# Encoder_AFE_incremental.net
KiCad netlist of a schematic drawn in Altium Designer
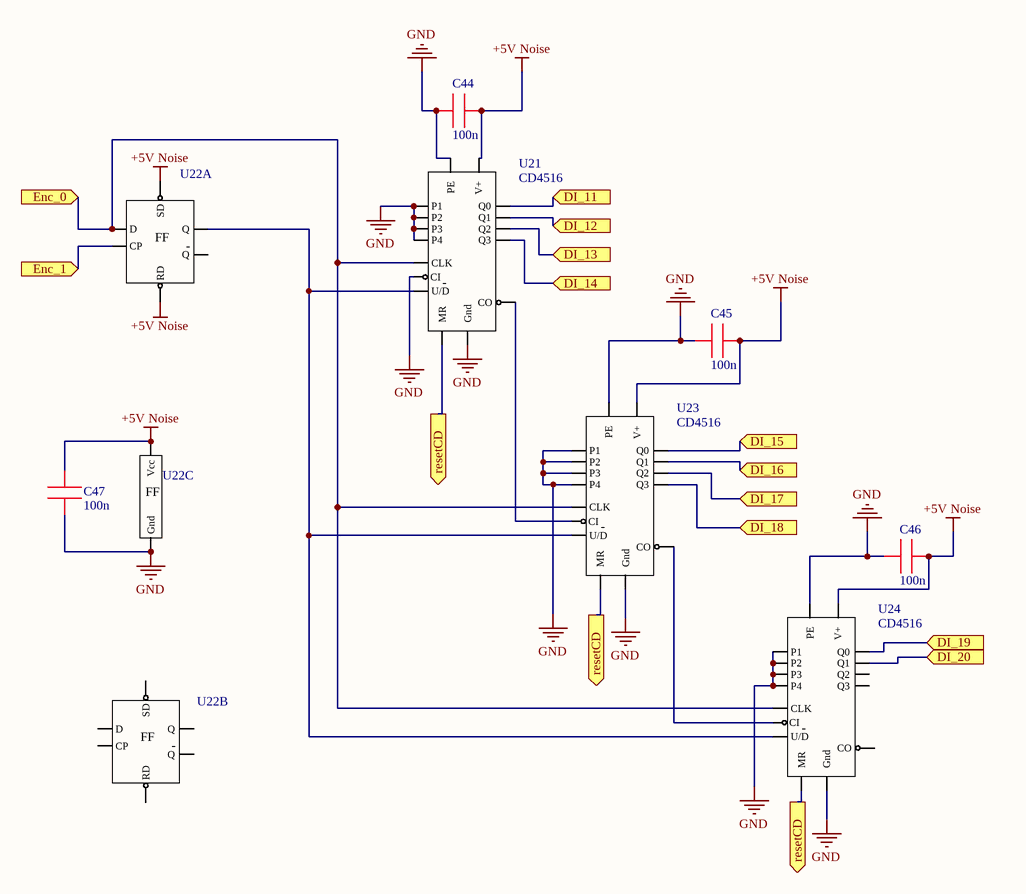
[diagram p0: Encoder AFE incremental.SchDoc]

(export (version "E")
  (design (tool "Eeschema 10.0.6"))
  (components
    (comp (ref "C44")
      (value "100n")
      (footprint "0603")
      (description "CC0603KRX7R9BB104")
      (libsource (lib "kontr") (part "0603 CAP"))
    )
    (comp (ref "C45")
      (value "100n")
      (footprint "0603")
      (description "CC0603KRX7R9BB104")
      (libsource (lib "kontr") (part "0603 CAP"))
    )
    (comp (ref "C46")
      (value "100n")
      (footprint "0603")
      (description "CC0603KRX7R9BB104")
      (libsource (lib "kontr") (part "0603 CAP"))
    )
    (comp (ref "C47")
      (value "100n")
      (footprint "0603")
      (description "CC0603KRX7R9BB104")
      (libsource (lib "kontr") (part "0603 CAP"))
    )
    (comp (ref "U21") (value "CD4516") (footprint "TSSOP-16") (libsource (lib "kontr") (part "CD4516")))
    (comp (ref "U22")
      (value "74HC74D")
      (footprint "SOIC 14 lead")
      (description "74HC74D,653")
      (libsource (lib "kontr") (part "74HC74D"))
    )
    (comp (ref "U23") (value "CD4516") (footprint "TSSOP-16") (libsource (lib "kontr") (part "CD4516")))
    (comp (ref "U24") (value "CD4516") (footprint "TSSOP-16") (libsource (lib "kontr") (part "CD4516")))
  )
  (nets
    (net (code "1") (name "+5V Noise") (class "Default")
      (node (ref "C44") (pin "2") (pinfunction "2_2") (pintype "passive"))
      (node (ref "C45") (pin "2") (pinfunction "2_2") (pintype "passive"))
      (node (ref "C46") (pin "2") (pinfunction "2_2") (pintype "passive"))
      (node (ref "C47") (pin "2") (pinfunction "2_2") (pintype "passive"))
      (node (ref "U21") (pin "16") (pinfunction "V+_16") (pintype "passive"))
      (node (ref "U22") (pin "1") (pinfunction "RD_1") (pintype "passive"))
      (node (ref "U22") (pin "14") (pinfunction "Vcc_14") (pintype "passive"))
      (node (ref "U22") (pin "4") (pinfunction "SD_4") (pintype "passive"))
      (node (ref "U23") (pin "16") (pinfunction "V+_16") (pintype "passive"))
      (node (ref "U24") (pin "16") (pinfunction "V+_16") (pintype "passive"))
    )
    (net (code "2") (name "/DI_11") (class "Default")
      (node (ref "U21") (pin "6") (pinfunction "Q0_6") (pintype "passive"))
    )
    (net (code "3") (name "/DI_12") (class "Default")
      (node (ref "U21") (pin "11") (pinfunction "Q1_11") (pintype "passive"))
    )
    (net (code "4") (name "/DI_13") (class "Default")
      (node (ref "U21") (pin "14") (pinfunction "Q2_14") (pintype "passive"))
    )
    (net (code "5") (name "/DI_14") (class "Default")
      (node (ref "U21") (pin "2") (pinfunction "Q3_2") (pintype "passive"))
    )
    (net (code "6") (name "/DI_15") (class "Default")
      (node (ref "U23") (pin "6") (pinfunction "Q0_6") (pintype "passive"))
    )
    (net (code "7") (name "/DI_16") (class "Default")
      (node (ref "U23") (pin "11") (pinfunction "Q1_11") (pintype "passive"))
    )
    (net (code "8") (name "/DI_17") (class "Default")
      (node (ref "U23") (pin "14") (pinfunction "Q2_14") (pintype "passive"))
    )
    (net (code "9") (name "/DI_18") (class "Default")
      (node (ref "U23") (pin "2") (pinfunction "Q3_2") (pintype "passive"))
    )
    (net (code "10") (name "/DI_19") (class "Default")
      (node (ref "U24") (pin "6") (pinfunction "Q0_6") (pintype "passive"))
    )
    (net (code "11") (name "/DI_20") (class "Default")
      (node (ref "U24") (pin "11") (pinfunction "Q1_11") (pintype "passive"))
    )
    (net (code "12") (name "/Enc_0") (class "Default")
      (node (ref "U21") (pin "15") (pinfunction "CLK_15") (pintype "passive"))
      (node (ref "U22") (pin "2") (pinfunction "D_2") (pintype "passive"))
      (node (ref "U23") (pin "15") (pinfunction "CLK_15") (pintype "passive"))
      (node (ref "U24") (pin "15") (pinfunction "CLK_15") (pintype "passive"))
    )
    (net (code "13") (name "/Enc_1") (class "Default")
      (node (ref "U22") (pin "3") (pinfunction "CP_3") (pintype "passive"))
    )
    (net (code "14") (name "/resetCD") (class "Default")
      (node (ref "U21") (pin "9") (pinfunction "MR_9") (pintype "passive"))
      (node (ref "U23") (pin "9") (pinfunction "MR_9") (pintype "passive"))
      (node (ref "U24") (pin "9") (pinfunction "MR_9") (pintype "passive"))
    )
    (net (code "15") (name "GND") (class "Default")
      (node (ref "C44") (pin "1") (pinfunction "1_1") (pintype "passive"))
      (node (ref "C45") (pin "1") (pinfunction "1_1") (pintype "passive"))
      (node (ref "C46") (pin "1") (pinfunction "1_1") (pintype "passive"))
      (node (ref "C47") (pin "1") (pinfunction "1_1") (pintype "passive"))
      (node (ref "U21") (pin "1") (pinfunction "PE_1") (pintype "passive"))
      (node (ref "U21") (pin "12") (pinfunction "P2_12") (pintype "passive"))
      (node (ref "U21") (pin "13") (pinfunction "P3_13") (pintype "passive"))
      (node (ref "U21") (pin "3") (pinfunction "P4_3") (pintype "passive"))
      (node (ref "U21") (pin "4") (pinfunction "P1_4") (pintype "passive"))
      (node (ref "U21") (pin "5") (pinfunction "CI_5") (pintype "passive"))
      (node (ref "U21") (pin "8") (pinfunction "Gnd_8") (pintype "passive"))
      (node (ref "U22") (pin "7") (pinfunction "Gnd_7") (pintype "passive"))
      (node (ref "U23") (pin "1") (pinfunction "PE_1") (pintype "passive"))
      (node (ref "U23") (pin "12") (pinfunction "P2_12") (pintype "passive"))
      (node (ref "U23") (pin "13") (pinfunction "P3_13") (pintype "passive"))
      (node (ref "U23") (pin "3") (pinfunction "P4_3") (pintype "passive"))
      (node (ref "U23") (pin "4") (pinfunction "P1_4") (pintype "passive"))
      (node (ref "U23") (pin "8") (pinfunction "Gnd_8") (pintype "passive"))
      (node (ref "U24") (pin "1") (pinfunction "PE_1") (pintype "passive"))
      (node (ref "U24") (pin "12") (pinfunction "P2_12") (pintype "passive"))
      (node (ref "U24") (pin "13") (pinfunction "P3_13") (pintype "passive"))
      (node (ref "U24") (pin "3") (pinfunction "P4_3") (pintype "passive"))
      (node (ref "U24") (pin "4") (pinfunction "P1_4") (pintype "passive"))
      (node (ref "U24") (pin "8") (pinfunction "Gnd_8") (pintype "passive"))
    )
    (net (code "16") (name "Net-(U21-CO)") (class "Default")
      (node (ref "U21") (pin "7") (pinfunction "CO_7") (pintype "passive"))
      (node (ref "U23") (pin "5") (pinfunction "CI_5") (pintype "passive"))
    )
    (net (code "17") (name "Net-(U21-U{slash}D)") (class "Default")
      (node (ref "U21") (pin "10") (pinfunction "U/D_10") (pintype "passive"))
      (node (ref "U22") (pin "5") (pinfunction "Q_5") (pintype "passive"))
      (node (ref "U23") (pin "10") (pinfunction "U/D_10") (pintype "passive"))
      (node (ref "U24") (pin "10") (pinfunction "U/D_10") (pintype "passive"))
    )
    (net (code "18") (name "Net-(U23-CO)") (class "Default")
      (node (ref "U23") (pin "7") (pinfunction "CO_7") (pintype "passive"))
      (node (ref "U24") (pin "5") (pinfunction "CI_5") (pintype "passive"))
    )
    (net (code "19") (name "unconnected-(U22A-Q-Pad6)") (class "Default")
      (node (ref "U22") (pin "6") (pinfunction "Q_6") (pintype "passive"))
    )
    (net (code "20") (name "unconnected-(U22B-CP-Pad11)") (class "Default")
      (node (ref "U22") (pin "11") (pinfunction "CP_11") (pintype "passive"))
    )
    (net (code "21") (name "unconnected-(U22B-D-Pad12)") (class "Default")
      (node (ref "U22") (pin "12") (pinfunction "D_12") (pintype "passive"))
    )
    (net (code "22") (name "unconnected-(U22B-Q-Pad8)") (class "Default")
      (node (ref "U22") (pin "8") (pinfunction "Q_8") (pintype "passive"))
    )
    (net (code "23") (name "unconnected-(U22B-Q-Pad9)") (class "Default")
      (node (ref "U22") (pin "9") (pinfunction "Q_9") (pintype "passive"))
    )
    (net (code "24") (name "unconnected-(U22B-RD-Pad13)") (class "Default")
      (node (ref "U22") (pin "13") (pinfunction "RD_13") (pintype "passive"))
    )
    (net (code "25") (name "unconnected-(U22B-SD-Pad10)") (class "Default")
      (node (ref "U22") (pin "10") (pinfunction "SD_10") (pintype "passive"))
    )
    (net (code "26") (name "unconnected-(U24-CO-Pad7)") (class "Default")
      (node (ref "U24") (pin "7") (pinfunction "CO_7") (pintype "passive"))
    )
    (net (code "27") (name "unconnected-(U24-Q2-Pad14)") (class "Default")
      (node (ref "U24") (pin "14") (pinfunction "Q2_14") (pintype "passive"))
    )
    (net (code "28") (name "unconnected-(U24-Q3-Pad2)") (class "Default")
      (node (ref "U24") (pin "2") (pinfunction "Q3_2") (pintype "passive"))
    )
  )
)
